# max5025.net
KiCad netlist of a schematic drawn in Altium Designer
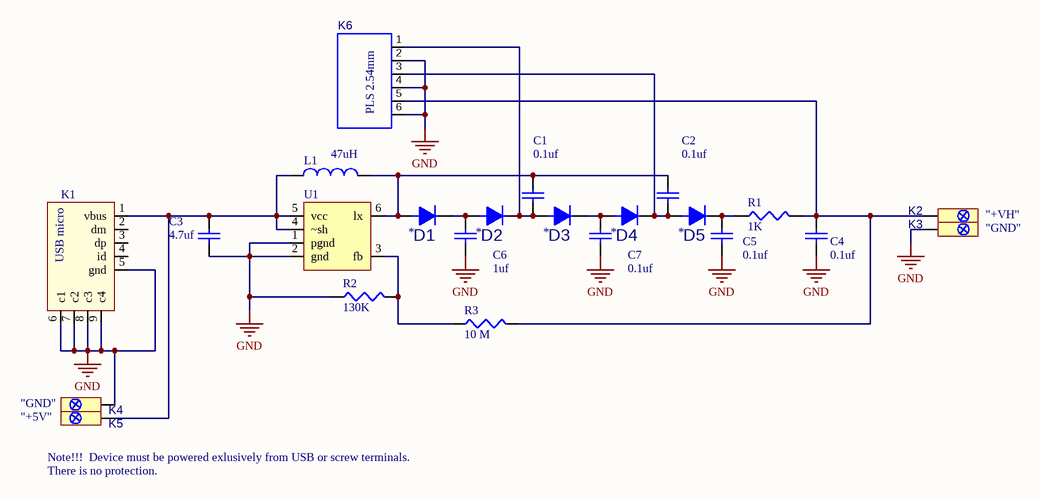
[diagram p0: max5025.SchDoc]

(export (version "E")
  (design (tool "Eeschema 10.0.6"))
  (components
    (comp (ref "C1")
      (value "0.1uf")
      (footprint "SM1206")
      (description "Capacitor")
      (fields (field (name "Comment") "cap1206") (field (name "PUBLISHER") "Altium Limited"))
      (libsource (lib "alt2017") (part "cap1206"))
    )
    (comp (ref "C2")
      (value "0.1uf")
      (footprint "SM1206")
      (description "Capacitor")
      (fields (field (name "Comment") "cap1206") (field (name "PUBLISHER") "Altium Limited"))
      (libsource (lib "alt2017") (part "cap1206"))
    )
    (comp (ref "C3")
      (value "4.7uf")
      (footprint "SM1206")
      (description "Capacitor")
      (fields (field (name "Comment") "cap1206") (field (name "PUBLISHER") "Altium Limited"))
      (libsource (lib "alt2017") (part "cap1206"))
    )
    (comp (ref "C4")
      (value "0.1uf")
      (footprint "SM1206")
      (description "Capacitor")
      (fields (field (name "Comment") "cap1206") (field (name "PUBLISHER") "Altium Limited"))
      (libsource (lib "alt2017") (part "cap1206"))
    )
    (comp (ref "C5")
      (value "0.1uf")
      (footprint "SM1206")
      (description "Capacitor")
      (fields (field (name "Comment") "cap1206") (field (name "PUBLISHER") "Altium Limited"))
      (libsource (lib "alt2017") (part "cap1206"))
    )
    (comp (ref "C6")
      (value "1uf")
      (footprint "SM1206")
      (description "Capacitor")
      (fields (field (name "Comment") "cap1206") (field (name "PUBLISHER") "Altium Limited"))
      (libsource (lib "alt2017") (part "cap1206"))
    )
    (comp (ref "C7")
      (value "0.1uf")
      (footprint "SM1206")
      (description "Capacitor")
      (fields (field (name "Comment") "cap1206") (field (name "PUBLISHER") "Altium Limited"))
      (libsource (lib "alt2017") (part "cap1206"))
    )
    (comp (ref "D1")
      (value "Diode")
      (footprint "SM1206_diode")
      (fields (field (name "ALTIUM_VALUE") "*"))
      (libsource (lib "alt2017") (part "Diode"))
    )
    (comp (ref "D2")
      (value "Diode")
      (footprint "SM1206_diode")
      (fields (field (name "ALTIUM_VALUE") "*"))
      (libsource (lib "alt2017") (part "Diode"))
    )
    (comp (ref "D3")
      (value "Diode")
      (footprint "SM1206_diode")
      (fields (field (name "ALTIUM_VALUE") "*"))
      (libsource (lib "alt2017") (part "Diode"))
    )
    (comp (ref "D4")
      (value "Diode")
      (footprint "SM1206_diode")
      (fields (field (name "ALTIUM_VALUE") "*"))
      (libsource (lib "alt2017") (part "Diode"))
    )
    (comp (ref "D5")
      (value "Diode")
      (footprint "SM1206_diode")
      (fields (field (name "ALTIUM_VALUE") "*"))
      (libsource (lib "alt2017") (part "Diode"))
    )
    (comp (ref "K1")
      (value "USB_micro")
      (footprint "USB_micro")
      (description "Sunrom")
      (libsource (lib "alt2017") (part "USB_micro"))
    )
    (comp (ref "K2") (value "SCREW_1") (footprint "SCREW_CON_8.1mm") (libsource (lib "") (part "SCREW_1_1")))
    (comp (ref "K3") (value "SCREW_1") (footprint "SCREW_CON_8.1mm") (libsource (lib "") (part "SCREW_1_1")))
    (comp (ref "K4")
      (value "SCREW_1")
      (footprint "SCREW_CON_8.1mm")
      (libsource (lib "alt2017") (part "SCREW_1"))
    )
    (comp (ref "K5")
      (value "SCREW_1")
      (footprint "SCREW_CON_8.1mm")
      (libsource (lib "alt2017") (part "SCREW_1"))
    )
    (comp (ref "K6")
      (value "2x3_PLS_2.54mm")
      (footprint "2x3 pin 2.54mm")
      (description "6 pin vertical 2x3 2.54mm")
      (libsource (lib "alt2017") (part "2x3_PLS_2.54mm"))
    )
    (comp (ref "L1")
      (value "inductance SMT 3.2x4.5 mm")
      (footprint "inductor_LQH43PN")
      (fields (field (name "ALTIUM_UNNAMED_1") "47uH"))
      (libsource (lib "alt2017") (part "inductor_LQH43PN"))
    )
    (comp (ref "R1")
      (value "1K")
      (footprint "SM0805")
      (description "Resistor")
      (fields (field (name "Comment") "res0805") (field (name "PUBLISHER") "Altium Limited"))
      (libsource (lib "alt2017") (part "res0805"))
    )
    (comp (ref "R2")
      (value "130K")
      (footprint "SM0805")
      (description "Resistor")
      (fields (field (name "Comment") "res0805") (field (name "PUBLISHER") "Altium Limited"))
      (libsource (lib "alt2017") (part "res0805"))
    )
    (comp (ref "R3")
      (value "10 M")
      (footprint "SM0805")
      (description "Resistor")
      (fields (field (name "Comment") "res0805") (field (name "PUBLISHER") "Altium Limited"))
      (libsource (lib "alt2017") (part "res0805"))
    )
    (comp (ref "U1")
      (value "boost conv")
      (footprint "SOT-23_6")
      (libsource (lib "alt2017") (part "MAX5025_sot23_6"))
    )
  )
  (nets
    (net (code "1") (name "GND") (class "Default")
      (node (ref "C3") (pin "1") (pinfunction "1_1") (pintype "passive"))
      (node (ref "C4") (pin "1") (pinfunction "1_1") (pintype "passive"))
      (node (ref "C5") (pin "1") (pinfunction "1_1") (pintype "passive"))
      (node (ref "C6") (pin "1") (pinfunction "1_1") (pintype "passive"))
      (node (ref "C7") (pin "1") (pinfunction "1_1") (pintype "passive"))
      (node (ref "K1") (pin "5") (pinfunction "gnd_5") (pintype "passive"))
      (node (ref "K1") (pin "6") (pinfunction "c1_6") (pintype "passive"))
      (node (ref "K1") (pin "7") (pinfunction "c2_7") (pintype "passive"))
      (node (ref "K1") (pin "8") (pinfunction "c3_8") (pintype "passive"))
      (node (ref "K1") (pin "9") (pinfunction "c4_9") (pintype "passive"))
      (node (ref "K3") (pin "1") (pinfunction "1_1") (pintype "passive"))
      (node (ref "K4") (pin "1") (pinfunction "1_1") (pintype "passive"))
      (node (ref "K6") (pin "2") (pinfunction "2_2") (pintype "passive"))
      (node (ref "K6") (pin "4") (pinfunction "4_4") (pintype "passive"))
      (node (ref "K6") (pin "6") (pinfunction "6_6") (pintype "passive"))
      (node (ref "R2") (pin "1") (pinfunction "1_1") (pintype "passive"))
      (node (ref "U1") (pin "1") (pinfunction "pgnd_1") (pintype "passive"))
      (node (ref "U1") (pin "2") (pinfunction "gnd_2") (pintype "passive"))
    )
    (net (code "2") (name "Net-(C4-Pad2)") (class "Default")
      (node (ref "C4") (pin "2") (pinfunction "2_2") (pintype "passive"))
      (node (ref "K2") (pin "1") (pinfunction "1_1") (pintype "passive"))
      (node (ref "K6") (pin "5") (pinfunction "5_5") (pintype "passive"))
      (node (ref "R1") (pin "2") (pinfunction "2_2") (pintype "passive"))
      (node (ref "R3") (pin "2") (pinfunction "2_2") (pintype "passive"))
    )
    (net (code "3") (name "Net-(D1-a)") (class "Default")
      (node (ref "C1") (pin "2") (pinfunction "2_2") (pintype "passive"))
      (node (ref "C2") (pin "2") (pinfunction "2_2") (pintype "passive"))
      (node (ref "D1") (pin "1") (pinfunction "a_1") (pintype "passive"))
      (node (ref "L1") (pin "2") (pinfunction "2_2") (pintype "passive"))
      (node (ref "U1") (pin "6") (pinfunction "lx_6") (pintype "passive"))
    )
    (net (code "4") (name "Net-(D1-k)") (class "Default")
      (node (ref "C6") (pin "2") (pinfunction "2_2") (pintype "passive"))
      (node (ref "D1") (pin "2") (pinfunction "k_2") (pintype "passive"))
      (node (ref "D2") (pin "1") (pinfunction "a_1") (pintype "passive"))
    )
    (net (code "5") (name "Net-(D2-k)") (class "Default")
      (node (ref "C1") (pin "1") (pinfunction "1_1") (pintype "passive"))
      (node (ref "D2") (pin "2") (pinfunction "k_2") (pintype "passive"))
      (node (ref "D3") (pin "1") (pinfunction "a_1") (pintype "passive"))
      (node (ref "K6") (pin "1") (pinfunction "1_1") (pintype "passive"))
    )
    (net (code "6") (name "Net-(D3-k)") (class "Default")
      (node (ref "C7") (pin "2") (pinfunction "2_2") (pintype "passive"))
      (node (ref "D3") (pin "2") (pinfunction "k_2") (pintype "passive"))
      (node (ref "D4") (pin "1") (pinfunction "a_1") (pintype "passive"))
    )
    (net (code "7") (name "Net-(D4-k)") (class "Default")
      (node (ref "C2") (pin "1") (pinfunction "1_1") (pintype "passive"))
      (node (ref "D4") (pin "2") (pinfunction "k_2") (pintype "passive"))
      (node (ref "D5") (pin "1") (pinfunction "a_1") (pintype "passive"))
      (node (ref "K6") (pin "3") (pinfunction "3_3") (pintype "passive"))
    )
    (net (code "8") (name "Net-(D5-k)") (class "Default")
      (node (ref "C5") (pin "2") (pinfunction "2_2") (pintype "passive"))
      (node (ref "D5") (pin "2") (pinfunction "k_2") (pintype "passive"))
      (node (ref "R1") (pin "1") (pinfunction "1_1") (pintype "passive"))
    )
    (net (code "9") (name "Net-(K1-vbus)") (class "Default")
      (node (ref "C3") (pin "2") (pinfunction "2_2") (pintype "passive"))
      (node (ref "K1") (pin "1") (pinfunction "vbus_1") (pintype "passive"))
      (node (ref "K5") (pin "1") (pinfunction "1_1") (pintype "passive"))
      (node (ref "L1") (pin "1") (pinfunction "1_1") (pintype "passive"))
      (node (ref "U1") (pin "4") (pinfunction "~sh_4") (pintype "passive"))
      (node (ref "U1") (pin "5") (pinfunction "vcc_5") (pintype "passive"))
    )
    (net (code "10") (name "Net-(U1-fb)") (class "Default")
      (node (ref "R2") (pin "2") (pinfunction "2_2") (pintype "passive"))
      (node (ref "R3") (pin "1") (pinfunction "1_1") (pintype "passive"))
      (node (ref "U1") (pin "3") (pinfunction "fb_3") (pintype "passive"))
    )
    (net (code "11") (name "unconnected-(K1-dm-Pad2)") (class "Default")
      (node (ref "K1") (pin "2") (pinfunction "dm_2") (pintype "passive"))
    )
    (net (code "12") (name "unconnected-(K1-dp-Pad3)") (class "Default")
      (node (ref "K1") (pin "3") (pinfunction "dp_3") (pintype "passive"))
    )
    (net (code "13") (name "unconnected-(K1-id-Pad4)") (class "Default")
      (node (ref "K1") (pin "4") (pinfunction "id_4") (pintype "passive"))
    )
  )
)
